# 02_-_SCH.net
KiCad netlist of a schematic drawn in Altium Designer
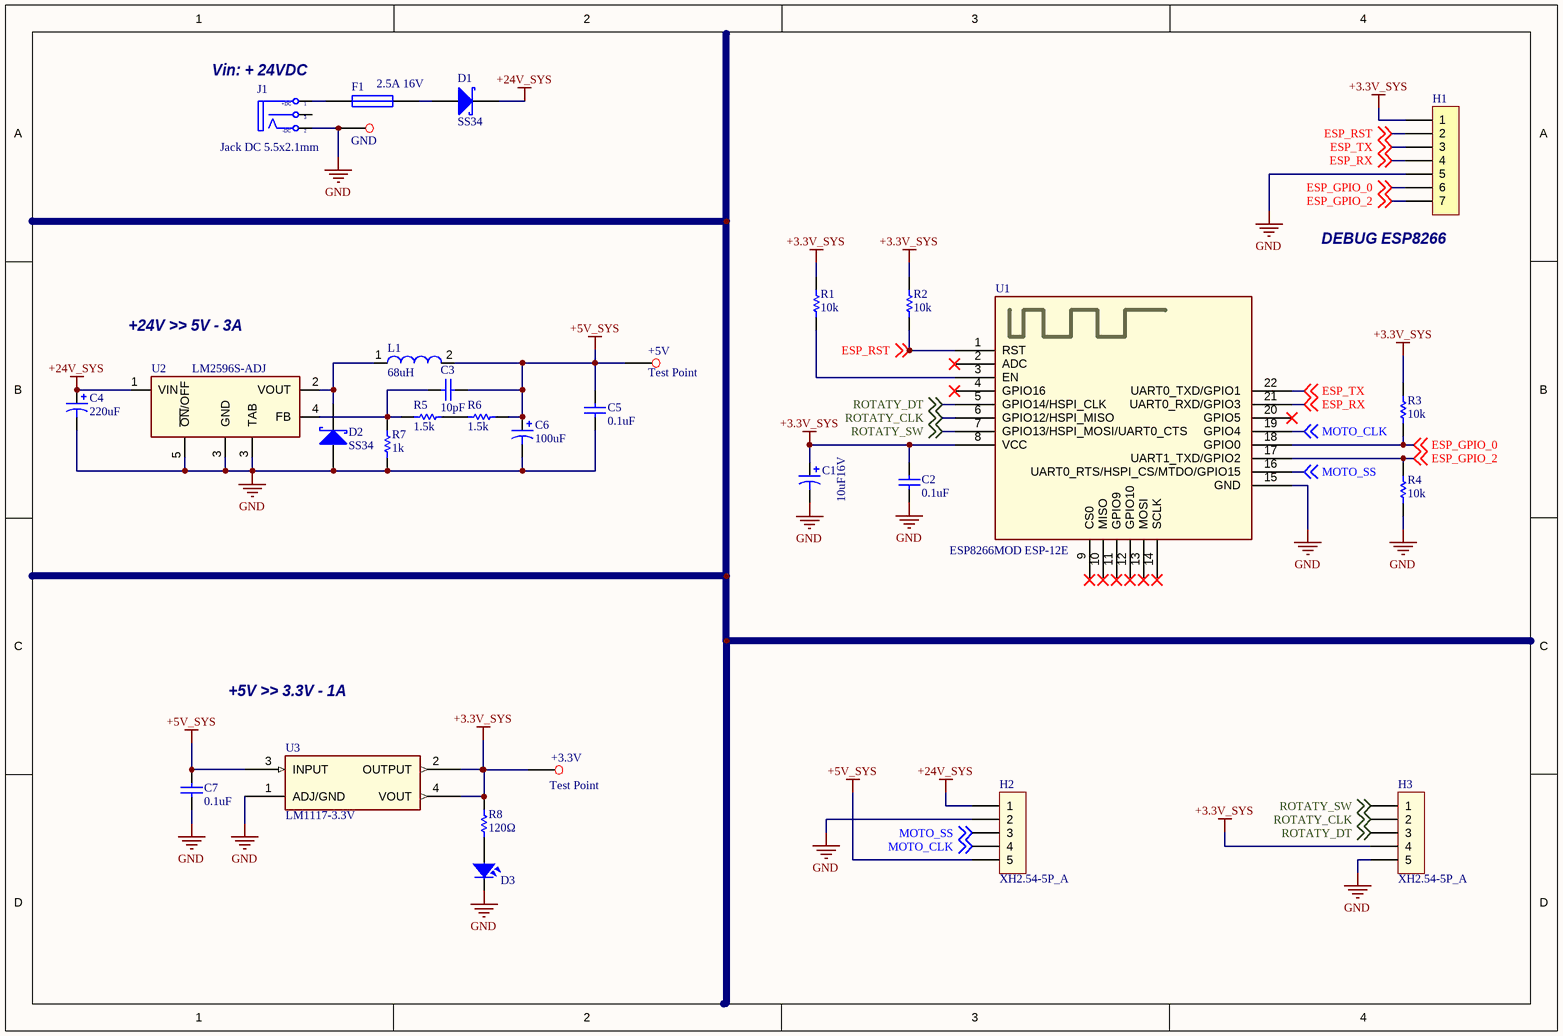
[diagram p0: [02] - SCH.SchDoc]

(export (version "E")
  (design (tool "Eeschema 10.0.6"))
  (components
    (comp (ref "+3.3V")
      (value "Test Point")
      (footprint "Test Point")
      (description "Test Point 1.6mm, SMD")
      (libsource (lib "eplusi") (part "Test Point"))
    )
    (comp (ref "+5V")
      (value "Test Point")
      (footprint "Test Point")
      (description "Test Point 1.6mm, SMD")
      (libsource (lib "eplusi") (part "Test Point"))
    )
    (comp (ref "C1")
      (value "10uF16V")
      (footprint "CAP TANTALUM TAJA 1206")
      (description "Capacitor Tantalum TAJA106K016RNJ, 10uF 16V 10%, 1206 SMD")
      (libsource (lib "ThanhNhan") (part "Cap Tantalum 1206 10uF16V"))
    )
    (comp (ref "C2")
      (value "0.1uF")
      (footprint "Cap 0603")
      (description "[LK00183]\r\nTụ điện Ceramic 0603 0.1uF, 50V, 10%")
      (libsource (lib "ThanhNhan") (part "Cap 0603 - 50V - 0.1uF"))
    )
    (comp (ref "C3")
      (value "10pF")
      (footprint "Cap 0603")
      (description "[LK00370]\r\nTụ điện Ceramic 0603 10pF, 50V, 5%")
      (libsource (lib "eplusi") (part "Cap 0603 - 50V - 10pF"))
    )
    (comp (ref "C4")
      (value "220uF")
      (footprint "Cap Aluminum UUD 10x10mm SMD")
      (description "[LK00306]\r\nTụ Aluminum 220uF 50V 20%, 10x10.5mm, SMD (UUD1H221MNL1GS Nichicon)")
      (libsource (lib "eplusi") (part "Cap Aluminum 50V - 220uF"))
    )
    (comp (ref "C5")
      (value "0.1uF")
      (footprint "Cap 0603")
      (description "[LK00183]\r\nTụ điện Ceramic 0603 0.1uF, 50V, 10%")
      (libsource (lib "eplusi") (part "Cap 0603 - 50V - 0.1uF"))
    )
    (comp (ref "C6")
      (value "100uF")
      (footprint "Cap Aluminum UUD 8x10mm SMD")
      (description "[LK00305]\r\nTụ Aluminum 100uF 50V 20%, 8x10.5mm, SMD (UUD1V101MNL1GS Nichicon)")
      (libsource (lib "eplusi") (part "Cap Aluminum 50V - 100uF"))
    )
    (comp (ref "C7")
      (value "0.1uF")
      (footprint "Cap 0603")
      (description "[LK00183]\r\nTụ điện Ceramic 0603 0.1uF, 50V, 10%")
      (libsource (lib "eplusi") (part "Cap 0603 - 50V - 0.1uF"))
    )
    (comp (ref "D1")
      (value "SS34")
      (footprint "DO-214AC")
      (description "[LK00095]\r\nDiode Schottky SS34, Small Signal Schottky Diode, Vrrm=40V, If=3A, SOD-80 SMD")
      (libsource (lib "ThanhNhan") (part "Diode Schottky SS34"))
    )
    (comp (ref "D2")
      (value "SS34")
      (footprint "DO-214AC")
      (description "[LK00087]\r\nDiode Schottky SS34, Small Signal Schottky Diode, Vrrm=40V, If=3A, SOD-80 SMD")
      (libsource (lib "eplusi") (part "Diode Schottky SS34"))
    )
    (comp (ref "D3")
      (value "LED")
      (footprint "ThanhNhan:LED 0805-A")
      (description "LED 0805 SMD Green")
      (libsource (lib "ThanhNhan") (part "LED 0805 SMD"))
    )
    (comp (ref "F1")
      (value "2.5A 16V")
      (footprint "Fuse 1812")
      (description "[LK00218]\r\nFuse PTC MF-MSMF250/16X, 2.5A 16V, 1812 SMD")
      (libsource (lib "ThanhNhan") (part "Fuse 1812 2.5A 16V"))
    )
    (comp (ref "GND")
      (value "Test Point")
      (footprint "Test Point")
      (description "Test Point 1.6mm, SMD")
      (libsource (lib "eplusi") (part "Test Point"))
    )
    (comp (ref "H1")
      (value "Header 2.54mm 1x7PIN")
      (footprint "Header 2.54MM 1x7PIN 180")
      (description "Header male 2.54mm, 1x7PIN, 180 Degrees DIP")
      (libsource (lib "ThanhNhan") (part "Header 2.54mm 1x7PIN 180"))
    )
    (comp (ref "H2")
      (value "XH2.54-5P_A")
      (footprint "XH2.54-5P_A")
      (description "Bus, XH2.54-5PIN 2.54mm, 180 Degrees DIP")
      (libsource (lib "ThanhNhan") (part "XH2.54-5P_A"))
    )
    (comp (ref "H3")
      (value "XH2.54-5P_A")
      (footprint "XH2.54-5P_A")
      (description "Bus, XH2.54-5PIN 2.54mm, 180 Degrees DIP")
      (libsource (lib "ThanhNhan") (part "XH2.54-5P_A"))
    )
    (comp (ref "J1")
      (value "Jack DC 5.5x2.1mm")
      (footprint "JACK DC 5.5x2.1mm")
      (libsource (lib "ThanhNhan") (part "Jack DC 5.5x2.1mm"))
    )
    (comp (ref "L1")
      (value "68uH")
      (footprint "Inductor CDRH127")
      (description "[LK00261]\r\nInductor CDRH127 68uH, 12X12X8mm, SMD")
      (libsource (lib "eplusi") (part "Inductor CDRH127 68uH"))
    )
    (comp (ref "R1")
      (value "10k")
      (footprint "Res 0603")
      (description "[LK00053]\r\nResistor 0603, 10k, 1%, 1/10W")
      (libsource (lib "ThanhNhan") (part "Res 0603 - 1% - 10k"))
    )
    (comp (ref "R2")
      (value "10k")
      (footprint "Res 0603")
      (description "[LK00053]\r\nResistor 0603, 10k, 1%, 1/10W")
      (libsource (lib "ThanhNhan") (part "Res 0603 - 1% - 10k"))
    )
    (comp (ref "R3")
      (value "10k")
      (footprint "Res 0603")
      (description "[LK00053]\r\nResistor 0603, 10k, 1%, 1/10W")
      (libsource (lib "ThanhNhan") (part "Res 0603 - 1% - 10k"))
    )
    (comp (ref "R4")
      (value "10k")
      (footprint "Res 0603")
      (description "[LK00053]\r\nResistor 0603, 10k, 1%, 1/10W")
      (libsource (lib "ThanhNhan") (part "Res 0603 - 1% - 10k"))
    )
    (comp (ref "R5")
      (value "1.5k")
      (footprint "Res 0603")
      (description "[LK00050]\r\nResistor 0603, 1.5k, 1%, 1/10W")
      (libsource (lib "eplusi") (part "Res 0603 - 1% - 1.5k"))
    )
    (comp (ref "R6")
      (value "1.5k")
      (footprint "Res 0603")
      (description "[LK00050]\r\nResistor 0603, 1.5k, 1%, 1/10W")
      (libsource (lib "eplusi") (part "Res 0603 - 1% - 1.5k"))
    )
    (comp (ref "R7")
      (value "1k")
      (footprint "Res 0603")
      (description "[LK00054]\r\nResistor 0603, 1k, 1%, 1/10W")
      (libsource (lib "eplusi") (part "Res 0603 - 1% - 1k"))
    )
    (comp (ref "R8")
      (value "120Ω")
      (footprint "Res 0603")
      (description "[LK00234]\r\nResistor 0603 120R, 5%, 1/10W")
      (libsource (lib "ThanhNhan") (part "Res 0603 - 5% - 120Ω"))
    )
    (comp (ref "U1")
      (value "ESP8266MOD ESP-12E")
      (footprint "Module ESP8266MOD ESP-12E")
      (description "Module ESP8266MOD ESP-12E, SDIO 2.0-SPI-UART, 802.11b/g/n, 4MB Flash, 3-3.6V 80mA")
      (libsource (lib "ThanhNhan") (part "Module ESP8266MOD ESP-12E"))
    )
    (comp (ref "U2")
      (value "LM2596S-ADJ")
      (footprint "TO-263 5PIN")
      (description "[LK00299]\r\nIC Power LM2596S-ADJ, In Vmax 40V, Buck ADJ 3A, 1.23-37V, TO263-5 SMD")
      (libsource (lib "eplusi") (part "LM2596S-ADJ"))
    )
    (comp (ref "U3")
      (value "LM1117-3.3V")
      (footprint "SOT-223 4PIN")
      (description "IC LM1117-3.3V, 8mA, Vmax=20V, SOT-223")
      (libsource (lib "ThanhNhan") (part "Power LM1117-3.3V"))
    )
  )
  (nets
    (net (code "1") (name "+3.3V_SYS") (class "Default")
      (node (ref "+3.3V") (pin "1") (pinfunction "1_1") (pintype "passive"))
      (node (ref "C1") (pin "1") (pinfunction "1_1") (pintype "passive"))
      (node (ref "C2") (pin "2") (pinfunction "2_2") (pintype "passive"))
      (node (ref "H1") (pin "1") (pinfunction "1_1") (pintype "passive"))
      (node (ref "H3") (pin "4") (pinfunction "4_4") (pintype "passive"))
      (node (ref "R1") (pin "2") (pinfunction "2_2") (pintype "passive"))
      (node (ref "R2") (pin "2") (pinfunction "2_2") (pintype "passive"))
      (node (ref "R3") (pin "2") (pinfunction "2_2") (pintype "passive"))
      (node (ref "R8") (pin "2") (pinfunction "2_2") (pintype "passive"))
      (node (ref "U1") (pin "8") (pinfunction "VCC_8") (pintype "passive"))
      (node (ref "U3") (pin "2") (pinfunction "OUTPUT_2") (pintype "output"))
      (node (ref "U3") (pin "4") (pinfunction "VOUT_4") (pintype "output"))
    )
    (net (code "2") (name "+5V_SYS") (class "Default")
      (node (ref "+5V") (pin "1") (pinfunction "1_1") (pintype "passive"))
      (node (ref "C3") (pin "1") (pinfunction "1_1") (pintype "passive"))
      (node (ref "C5") (pin "2") (pinfunction "2_2") (pintype "passive"))
      (node (ref "C6") (pin "1") (pinfunction "1_1") (pintype "passive"))
      (node (ref "C7") (pin "2") (pinfunction "2_2") (pintype "passive"))
      (node (ref "H2") (pin "5") (pinfunction "5_5") (pintype "passive"))
      (node (ref "L1") (pin "2") (pinfunction "IN_2") (pintype "passive"))
      (node (ref "R6") (pin "2") (pinfunction "2_2") (pintype "passive"))
      (node (ref "U3") (pin "3") (pinfunction "INPUT_3") (pintype "input"))
    )
    (net (code "3") (name "+24V_SYS") (class "Default")
      (node (ref "C4") (pin "1") (pinfunction "1_1") (pintype "passive"))
      (node (ref "D1") (pin "2") (pinfunction "K_2") (pintype "passive"))
      (node (ref "H2") (pin "1") (pinfunction "1_1") (pintype "passive"))
      (node (ref "U2") (pin "1") (pinfunction "VIN_1") (pintype "passive"))
    )
    (net (code "4") (name "ESP_GPIO_0") (class "Default")
      (node (ref "H1") (pin "6") (pinfunction "6_6") (pintype "passive"))
      (node (ref "R3") (pin "1") (pinfunction "1_1") (pintype "passive"))
      (node (ref "U1") (pin "18") (pinfunction "GPIO0_18") (pintype "passive"))
    )
    (net (code "5") (name "ESP_GPIO_2") (class "Default")
      (node (ref "H1") (pin "7") (pinfunction "7_7") (pintype "passive"))
      (node (ref "R4") (pin "2") (pinfunction "2_2") (pintype "passive"))
      (node (ref "U1") (pin "17") (pinfunction "UART1_TXD/GPIO2_17") (pintype "passive"))
    )
    (net (code "6") (name "ESP_RST") (class "Default")
      (node (ref "H1") (pin "2") (pinfunction "2_2") (pintype "passive"))
      (node (ref "R2") (pin "1") (pinfunction "1_1") (pintype "passive"))
      (node (ref "U1") (pin "1") (pinfunction "RST_1") (pintype "passive"))
    )
    (net (code "7") (name "ESP_RX") (class "Default")
      (node (ref "H1") (pin "4") (pinfunction "4_4") (pintype "passive"))
      (node (ref "U1") (pin "21") (pinfunction "UART0_RXD/GPIO3_21") (pintype "passive"))
    )
    (net (code "8") (name "ESP_TX") (class "Default")
      (node (ref "H1") (pin "3") (pinfunction "3_3") (pintype "passive"))
      (node (ref "U1") (pin "22") (pinfunction "UART0_TXD/GPIO1_22") (pintype "passive"))
    )
    (net (code "9") (name "GND") (class "Default")
      (node (ref "C1") (pin "2") (pinfunction "2_2") (pintype "passive"))
      (node (ref "C2") (pin "1") (pinfunction "1_1") (pintype "passive"))
      (node (ref "C4") (pin "2") (pinfunction "2_2") (pintype "passive"))
      (node (ref "C5") (pin "1") (pinfunction "1_1") (pintype "passive"))
      (node (ref "C6") (pin "2") (pinfunction "2_2") (pintype "passive"))
      (node (ref "C7") (pin "1") (pinfunction "1_1") (pintype "passive"))
      (node (ref "D2") (pin "1") (pinfunction "A_1") (pintype "passive"))
      (node (ref "D3") (pin "2") (pinfunction "2_2") (pintype "passive"))
      (node (ref "GND") (pin "1") (pinfunction "1_1") (pintype "passive"))
      (node (ref "H1") (pin "5") (pinfunction "5_5") (pintype "passive"))
      (node (ref "H2") (pin "2") (pinfunction "2_2") (pintype "passive"))
      (node (ref "H3") (pin "5") (pinfunction "5_5") (pintype "passive"))
      (node (ref "J1") (pin "2") (pinfunction "TN_2") (pintype "passive"))
      (node (ref "R4") (pin "1") (pinfunction "1_1") (pintype "passive"))
      (node (ref "R7") (pin "1") (pinfunction "1_1") (pintype "passive"))
      (node (ref "U1") (pin "15") (pinfunction "GND_15") (pintype "passive"))
      (node (ref "U2") (pin "3") (pinfunction "TAB_3") (pintype "passive"))
      (node (ref "U2") (pin "5") (pinfunction "~{ON}/OFF_5") (pintype "passive"))
      (node (ref "U3") (pin "1") (pinfunction "ADJ/GND_1") (pintype "passive"))
    )
    (net (code "10") (name "MOTO_CLK") (class "Default")
      (node (ref "H2") (pin "4") (pinfunction "4_4") (pintype "passive"))
      (node (ref "U1") (pin "19") (pinfunction "GPIO4_19") (pintype "passive"))
    )
    (net (code "11") (name "MOTO_SS") (class "Default")
      (node (ref "H2") (pin "3") (pinfunction "3_3") (pintype "passive"))
      (node (ref "U1") (pin "16") (pinfunction "UART0_RTS/HSPI_CS/MTDO/GPIO15_16") (pintype "passive"))
    )
    (net (code "12") (name "Net-(D1-A)") (class "Default")
      (node (ref "D1") (pin "1") (pinfunction "A_1") (pintype "passive"))
      (node (ref "F1") (pin "2") (pinfunction "2_2") (pintype "passive"))
    )
    (net (code "13") (name "Net-(D2-K)") (class "Default")
      (node (ref "D2") (pin "2") (pinfunction "K_2") (pintype "passive"))
      (node (ref "L1") (pin "1") (pinfunction "IN_1") (pintype "passive"))
      (node (ref "U2") (pin "2") (pinfunction "VOUT_2") (pintype "passive"))
    )
    (net (code "14") (name "Net-(D3-Pad1)") (class "Default")
      (node (ref "D3") (pin "1") (pinfunction "1_1") (pintype "passive"))
      (node (ref "R8") (pin "1") (pinfunction "1_1") (pintype "passive"))
    )
    (net (code "15") (name "Net-(J1-T)") (class "Default")
      (node (ref "F1") (pin "1") (pinfunction "1_1") (pintype "passive"))
      (node (ref "J1") (pin "1") (pinfunction "T_1") (pintype "passive"))
    )
    (net (code "16") (name "Net-(R5-Pad2)") (class "Default")
      (node (ref "R5") (pin "2") (pinfunction "2_2") (pintype "passive"))
      (node (ref "R6") (pin "1") (pinfunction "1_1") (pintype "passive"))
    )
    (net (code "17") (name "Net-(U1-EN)") (class "Default")
      (node (ref "R1") (pin "1") (pinfunction "1_1") (pintype "passive"))
      (node (ref "U1") (pin "3") (pinfunction "EN_3") (pintype "passive"))
    )
    (net (code "18") (name "Net-(U2-FB)") (class "Default")
      (node (ref "C3") (pin "2") (pinfunction "2_2") (pintype "passive"))
      (node (ref "R5") (pin "1") (pinfunction "1_1") (pintype "passive"))
      (node (ref "R7") (pin "2") (pinfunction "2_2") (pintype "passive"))
      (node (ref "U2") (pin "4") (pinfunction "FB_4") (pintype "passive"))
    )
    (net (code "19") (name "ROTATY_CLK") (class "Default")
      (node (ref "H3") (pin "2") (pinfunction "2_2") (pintype "passive"))
      (node (ref "U1") (pin "6") (pinfunction "GPIO12/HSPI_MISO_6") (pintype "passive"))
    )
    (net (code "20") (name "ROTATY_DT") (class "Default")
      (node (ref "H3") (pin "3") (pinfunction "3_3") (pintype "passive"))
      (node (ref "U1") (pin "5") (pinfunction "GPIO14/HSPI_CLK_5") (pintype "passive"))
    )
    (net (code "21") (name "ROTATY_SW") (class "Default")
      (node (ref "H3") (pin "1") (pinfunction "1_1") (pintype "passive"))
      (node (ref "U1") (pin "7") (pinfunction "GPIO13/HSPI_MOSI/UART0_CTS_7") (pintype "passive"))
    )
    (net (code "22") (name "unconnected-(J1-S-Pad3)") (class "Default")
      (node (ref "J1") (pin "3") (pinfunction "S_3") (pintype "power_in"))
    )
    (net (code "23") (name "unconnected-(U1-ADC-Pad2)") (class "Default")
      (node (ref "U1") (pin "2") (pinfunction "ADC_2") (pintype "passive+no_connect"))
    )
    (net (code "24") (name "unconnected-(U1-CS0-Pad9)") (class "Default")
      (node (ref "U1") (pin "9") (pinfunction "CS0_9") (pintype "passive+no_connect"))
    )
    (net (code "25") (name "unconnected-(U1-GPIO5-Pad20)") (class "Default")
      (node (ref "U1") (pin "20") (pinfunction "GPIO5_20") (pintype "passive+no_connect"))
    )
    (net (code "26") (name "unconnected-(U1-GPIO9-Pad11)") (class "Default")
      (node (ref "U1") (pin "11") (pinfunction "GPIO9_11") (pintype "passive+no_connect"))
    )
    (net (code "27") (name "unconnected-(U1-GPIO10-Pad12)") (class "Default")
      (node (ref "U1") (pin "12") (pinfunction "GPIO10_12") (pintype "passive+no_connect"))
    )
    (net (code "28") (name "unconnected-(U1-GPIO16-Pad4)") (class "Default")
      (node (ref "U1") (pin "4") (pinfunction "GPIO16_4") (pintype "passive+no_connect"))
    )
    (net (code "29") (name "unconnected-(U1-MISO-Pad10)") (class "Default")
      (node (ref "U1") (pin "10") (pinfunction "MISO_10") (pintype "passive+no_connect"))
    )
    (net (code "30") (name "unconnected-(U1-MOSI-Pad13)") (class "Default")
      (node (ref "U1") (pin "13") (pinfunction "MOSI_13") (pintype "passive+no_connect"))
    )
    (net (code "31") (name "unconnected-(U1-SCLK-Pad14)") (class "Default")
      (node (ref "U1") (pin "14") (pinfunction "SCLK_14") (pintype "passive+no_connect"))
    )
  )
)
